# blinkm_mk2k.net
KiCad netlist of a schematic drawn in EAGLE
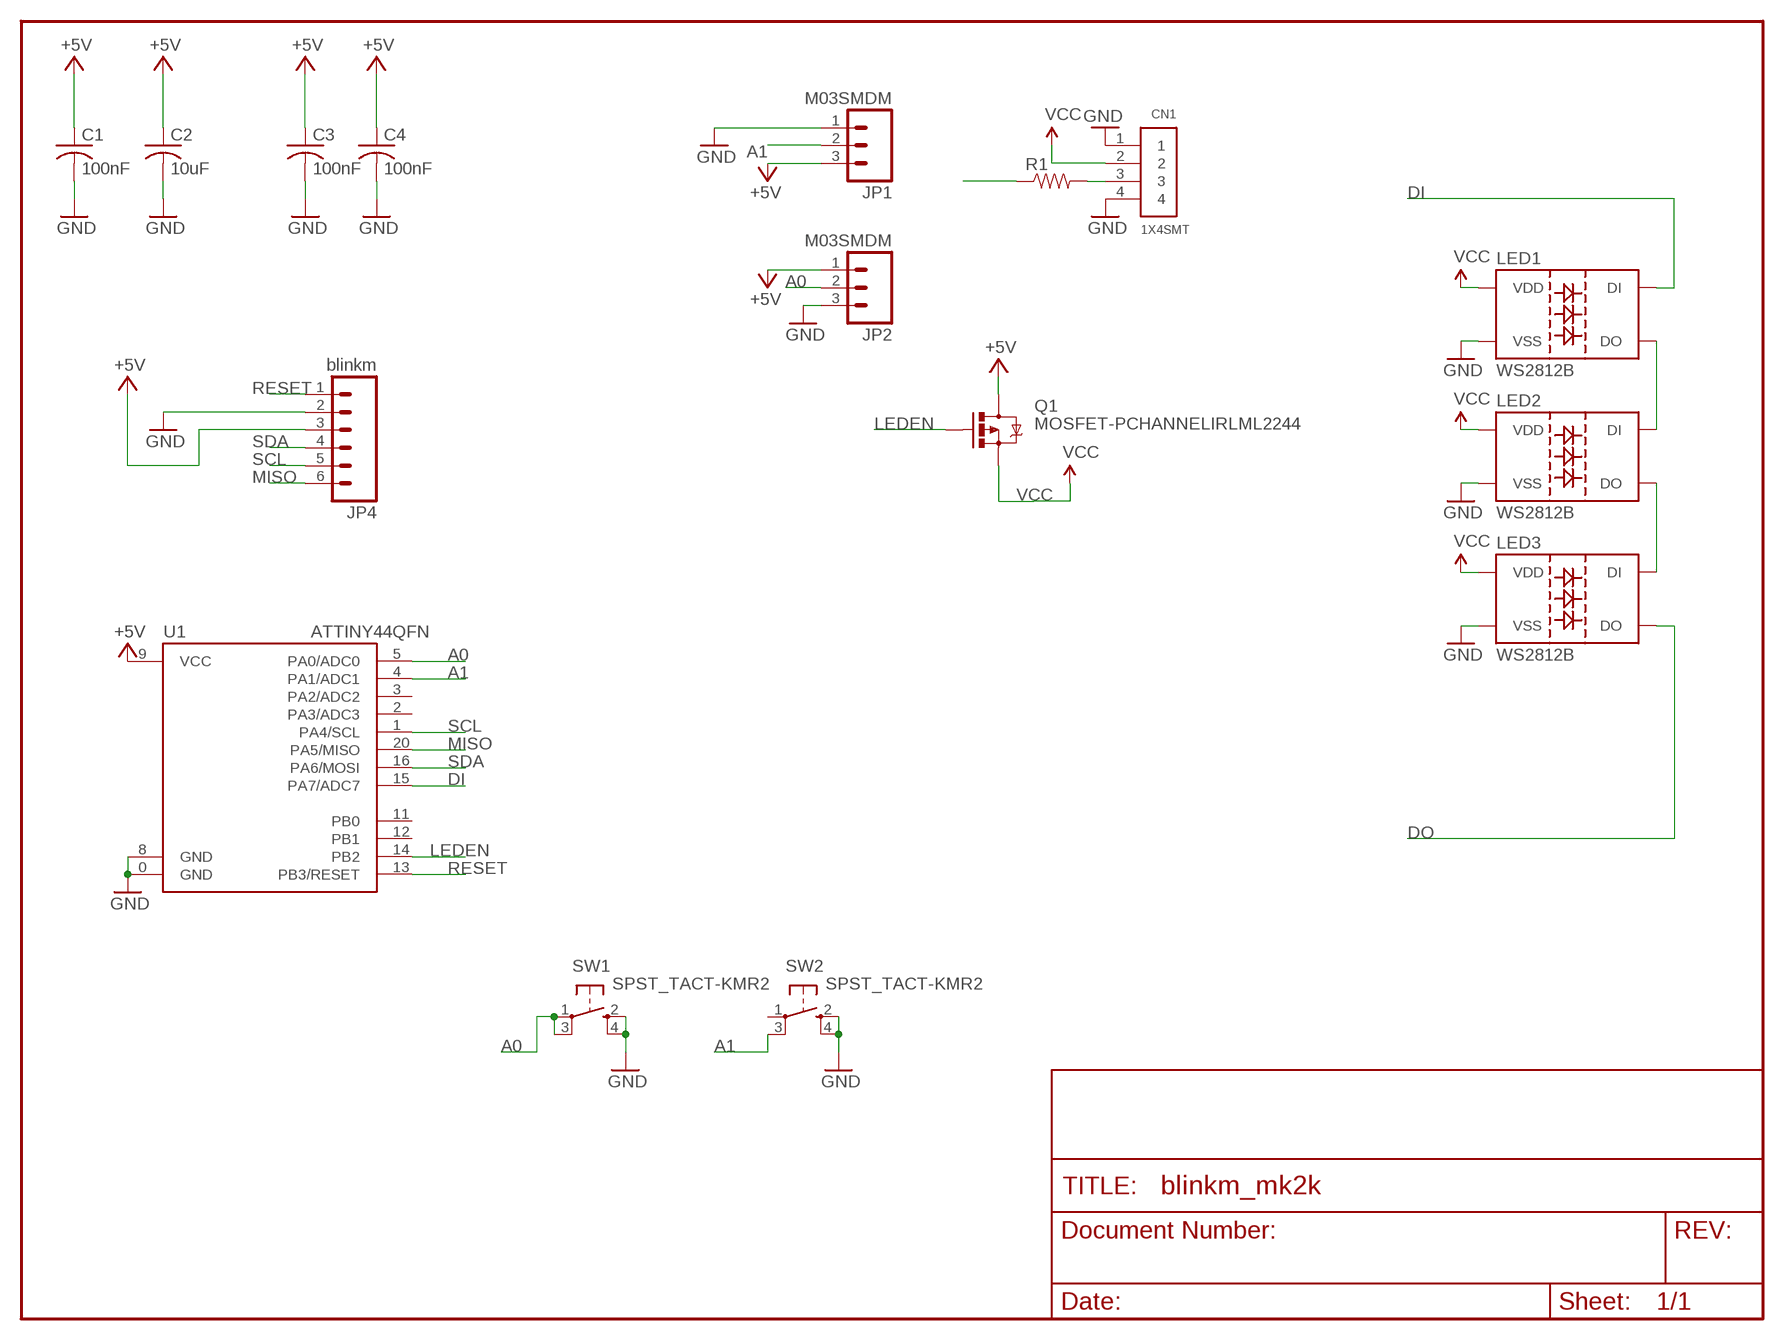
[diagram p0: schematic, sheet 1]

(export (version "E")
  (design (tool "Eeschema 10.0.6"))
  (components
    (comp (ref "C1")
      (value "100nF")
      (footprint "eagle-import:C0603")
      (libsource (lib "eagle-import") (part "C-USC0603"))
    )
    (comp (ref "C2")
      (value "10uF")
      (footprint "eagle-import:C0603")
      (libsource (lib "eagle-import") (part "C-USC0603"))
    )
    (comp (ref "C3")
      (value "100nF")
      (footprint "eagle-import:C0603")
      (libsource (lib "eagle-import") (part "C-USC0603"))
    )
    (comp (ref "C4")
      (value "100nF")
      (footprint "eagle-import:C0603")
      (libsource (lib "eagle-import") (part "C-USC0603"))
    )
    (comp (ref "CN1")
      (value "1X4SMT")
      (footprint "eagle-import:1X4-SMT")
      (libsource (lib "eagle-import") (part "1X4SMT"))
    )
    (comp (ref "JP1")
      (value "M03SMDM")
      (footprint "eagle-import:1X03-SMD-MINIMAL")
      (libsource (lib "eagle-import") (part "M03SMDM"))
    )
    (comp (ref "JP2")
      (value "M03SMDM")
      (footprint "eagle-import:1X03-SMD-MINIMAL")
      (libsource (lib "eagle-import") (part "M03SMDM"))
    )
    (comp (ref "JP4")
      (value "blinkm")
      (footprint "eagle-import:1X06_LOCK")
      (libsource (lib "eagle-import") (part "M06LOCK"))
    )
    (comp (ref "LED1")
      (value "WS2812B")
      (footprint "eagle-import:WS2812B")
      (libsource (lib "eagle-import") (part "WS2812B"))
    )
    (comp (ref "LED2")
      (value "WS2812B")
      (footprint "eagle-import:WS2812B")
      (libsource (lib "eagle-import") (part "WS2812B"))
    )
    (comp (ref "LED3")
      (value "WS2812B")
      (footprint "eagle-import:WS2812B")
      (libsource (lib "eagle-import") (part "WS2812B"))
    )
    (comp (ref "Q1")
      (value "MOSFET-PCHANNELIRLML2244")
      (footprint "eagle-import:SOT23-3")
      (libsource (lib "eagle-import") (part "MOSFET-PCHANNELIRLML2244"))
    )
    (comp (ref "R1")
      (value "RESISTOR0603")
      (footprint "eagle-import:0603-RES")
      (libsource (lib "eagle-import") (part "RESISTOR0603"))
    )
    (comp (ref "SW1")
      (value "SPST_TACT-KMR2")
      (footprint "eagle-import:KMR2")
      (libsource (lib "eagle-import") (part "SPST_TACT-KMR2"))
    )
    (comp (ref "SW2")
      (value "SPST_TACT-KMR2")
      (footprint "eagle-import:KMR2")
      (libsource (lib "eagle-import") (part "SPST_TACT-KMR2"))
    )
    (comp (ref "U1")
      (value "ATTINY44QFN")
      (footprint "eagle-import:QFN20")
      (libsource (lib "eagle-import") (part "ATTINY24QFN"))
    )
  )
  (nets
    (net (code "1") (name "+5V") (class "Default")
      (node (ref "C1") (pin "1") (pinfunction "1_1") (pintype "passive"))
      (node (ref "C2") (pin "1") (pinfunction "1_1") (pintype "passive"))
      (node (ref "C3") (pin "1") (pinfunction "1_1") (pintype "passive"))
      (node (ref "C4") (pin "1") (pinfunction "1_1") (pintype "passive"))
      (node (ref "JP1") (pin "3") (pinfunction "3_3") (pintype "passive"))
      (node (ref "JP2") (pin "1") (pinfunction "1_1") (pintype "passive"))
      (node (ref "JP4") (pin "3") (pinfunction "3_3") (pintype "passive"))
      (node (ref "Q1") (pin "3") (pinfunction "D_3") (pintype "passive"))
      (node (ref "U1") (pin "9") (pinfunction "VCC_9") (pintype "bidirectional"))
    )
    (net (code "2") (name "/A0") (class "Default")
      (node (ref "JP2") (pin "2") (pinfunction "2_2") (pintype "passive"))
      (node (ref "SW1") (pin "1") (pinfunction "P_1") (pintype "passive"))
      (node (ref "SW1") (pin "3") (pinfunction "P1_3") (pintype "passive"))
      (node (ref "U1") (pin "5") (pinfunction "PA0/ADC0_5") (pintype "bidirectional"))
    )
    (net (code "3") (name "/A1") (class "Default")
      (node (ref "JP1") (pin "2") (pinfunction "2_2") (pintype "passive"))
      (node (ref "SW2") (pin "3") (pinfunction "P1_3") (pintype "passive"))
      (node (ref "U1") (pin "4") (pinfunction "PA1/ADC1_4") (pintype "bidirectional"))
    )
    (net (code "4") (name "/DI") (class "Default")
      (node (ref "LED1") (pin "4") (pinfunction "DI_4") (pintype "bidirectional"))
      (node (ref "R1") (pin "1") (pinfunction "1_1") (pintype "passive"))
      (node (ref "U1") (pin "15") (pinfunction "PA7/ADC7_15") (pintype "bidirectional"))
    )
    (net (code "5") (name "/DO") (class "Default")
      (node (ref "LED3") (pin "2") (pinfunction "DO_2") (pintype "bidirectional"))
    )
    (net (code "6") (name "/LEDEN") (class "Default")
      (node (ref "Q1") (pin "1") (pinfunction "G_1") (pintype "passive"))
      (node (ref "U1") (pin "14") (pinfunction "PB2_14") (pintype "bidirectional"))
    )
    (net (code "7") (name "/MISO") (class "Default")
      (node (ref "JP4") (pin "6") (pinfunction "6_6") (pintype "passive"))
      (node (ref "U1") (pin "20") (pinfunction "PA5/MISO_20") (pintype "bidirectional"))
    )
    (net (code "8") (name "/RESET") (class "Default")
      (node (ref "JP4") (pin "1") (pinfunction "1_1") (pintype "passive"))
      (node (ref "U1") (pin "13") (pinfunction "PB3/RESET_13") (pintype "bidirectional"))
    )
    (net (code "9") (name "/SCL") (class "Default")
      (node (ref "JP4") (pin "5") (pinfunction "5_5") (pintype "passive"))
      (node (ref "U1") (pin "1") (pinfunction "PA4/SCL_1") (pintype "bidirectional"))
    )
    (net (code "10") (name "/SDA") (class "Default")
      (node (ref "JP4") (pin "4") (pinfunction "4_4") (pintype "passive"))
      (node (ref "U1") (pin "16") (pinfunction "PA6/MOSI_16") (pintype "bidirectional"))
    )
    (net (code "11") (name "GND") (class "Default")
      (node (ref "C1") (pin "2") (pinfunction "2_2") (pintype "passive"))
      (node (ref "C2") (pin "2") (pinfunction "2_2") (pintype "passive"))
      (node (ref "C3") (pin "2") (pinfunction "2_2") (pintype "passive"))
      (node (ref "C4") (pin "2") (pinfunction "2_2") (pintype "passive"))
      (node (ref "CN1") (pin "1") (pinfunction "1_1") (pintype "bidirectional"))
      (node (ref "CN1") (pin "4") (pinfunction "4_4") (pintype "bidirectional"))
      (node (ref "JP1") (pin "1") (pinfunction "1_1") (pintype "passive"))
      (node (ref "JP2") (pin "3") (pinfunction "3_3") (pintype "passive"))
      (node (ref "JP4") (pin "2") (pinfunction "2_2") (pintype "passive"))
      (node (ref "LED1") (pin "3") (pinfunction "VSS_3") (pintype "bidirectional"))
      (node (ref "LED2") (pin "3") (pinfunction "VSS_3") (pintype "bidirectional"))
      (node (ref "LED3") (pin "3") (pinfunction "VSS_3") (pintype "bidirectional"))
      (node (ref "SW1") (pin "2") (pinfunction "S_2") (pintype "passive"))
      (node (ref "SW1") (pin "4") (pinfunction "S1_4") (pintype "passive"))
      (node (ref "SW2") (pin "2") (pinfunction "S_2") (pintype "passive"))
      (node (ref "SW2") (pin "4") (pinfunction "S1_4") (pintype "passive"))
      (node (ref "U1") (pin "0") (pinfunction "GND_0") (pintype "bidirectional"))
      (node (ref "U1") (pin "8") (pinfunction "GND_8") (pintype "bidirectional"))
    )
    (net (code "12") (name "Net-(CN1-Pad3)") (class "Default")
      (node (ref "CN1") (pin "3") (pinfunction "3_3") (pintype "bidirectional"))
      (node (ref "R1") (pin "2") (pinfunction "2_2") (pintype "passive"))
    )
    (net (code "13") (name "Net-(LED1-DO)") (class "Default")
      (node (ref "LED1") (pin "2") (pinfunction "DO_2") (pintype "bidirectional"))
      (node (ref "LED2") (pin "4") (pinfunction "DI_4") (pintype "bidirectional"))
    )
    (net (code "14") (name "Net-(LED2-DO)") (class "Default")
      (node (ref "LED2") (pin "2") (pinfunction "DO_2") (pintype "bidirectional"))
      (node (ref "LED3") (pin "4") (pinfunction "DI_4") (pintype "bidirectional"))
    )
    (net (code "15") (name "VCC") (class "Default")
      (node (ref "CN1") (pin "2") (pinfunction "2_2") (pintype "bidirectional"))
      (node (ref "LED1") (pin "1") (pinfunction "VDD_1") (pintype "bidirectional"))
      (node (ref "LED2") (pin "1") (pinfunction "VDD_1") (pintype "bidirectional"))
      (node (ref "LED3") (pin "1") (pinfunction "VDD_1") (pintype "bidirectional"))
      (node (ref "Q1") (pin "2") (pinfunction "S_2") (pintype "passive"))
    )
    (net (code "16") (name "unconnected-(SW2-P-Pad1)") (class "Default")
      (node (ref "SW2") (pin "1") (pinfunction "P_1") (pintype "passive"))
    )
    (net (code "17") (name "unconnected-(U1-PA2{slash}ADC2-Pad3)") (class "Default")
      (node (ref "U1") (pin "3") (pinfunction "PA2/ADC2_3") (pintype "bidirectional"))
    )
    (net (code "18") (name "unconnected-(U1-PA3{slash}ADC3-Pad2)") (class "Default")
      (node (ref "U1") (pin "2") (pinfunction "PA3/ADC3_2") (pintype "bidirectional"))
    )
    (net (code "19") (name "unconnected-(U1-PB0-Pad11)") (class "Default")
      (node (ref "U1") (pin "11") (pinfunction "PB0_11") (pintype "bidirectional"))
    )
    (net (code "20") (name "unconnected-(U1-PB1-Pad12)") (class "Default")
      (node (ref "U1") (pin "12") (pinfunction "PB1_12") (pintype "bidirectional"))
    )
  )
)
